# inertial.net
KiCad netlist of a schematic drawn in Altium Designer
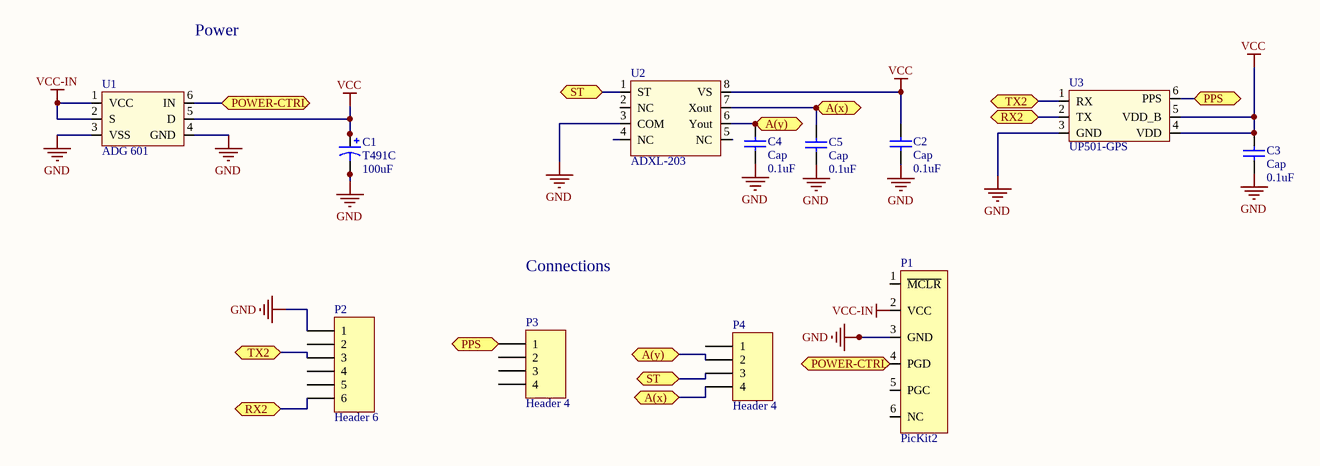
[diagram p0: inertial.SchDoc]

(export (version "E")
  (design (tool "Eeschema 10.0.6"))
  (components
    (comp (ref "C1")
      (value "T491C")
      (footprint "C")
      (description "Solid Tantalum Chip Capacitor, Standard T491 Series - Industrial Grade")
      (fields (field (name "ALTIUM_VALUE") "100uF") (field (name "PUBLISHER") "Altium Limited"))
      (libsource (lib "KEMET Chip Capacitor") (part "T491C"))
    )
    (comp (ref "C2")
      (value "Cap")
      (footprint "C1206")
      (description "Capacitor")
      (fields (field (name "ALTIUM_VALUE") "0.1uF") (field (name "PUBLISHER") "Altium Limited"))
      (libsource (lib "Miscellaneous Devices") (part "Cap"))
    )
    (comp (ref "C3")
      (value "Cap")
      (footprint "C1206")
      (description "Capacitor")
      (fields (field (name "ALTIUM_VALUE") "0.1uF") (field (name "PUBLISHER") "Altium Limited"))
      (libsource (lib "Miscellaneous Devices") (part "Cap"))
    )
    (comp (ref "C4")
      (value "Cap")
      (footprint "C1206")
      (description "Capacitor")
      (fields (field (name "ALTIUM_VALUE") "0.1uF") (field (name "PUBLISHER") "Altium Limited"))
      (libsource (lib "Miscellaneous Devices") (part "Cap"))
    )
    (comp (ref "C5")
      (value "Cap")
      (footprint "C1206")
      (description "Capacitor")
      (fields (field (name "ALTIUM_VALUE") "0.1uF") (field (name "PUBLISHER") "Altium Limited"))
      (libsource (lib "Miscellaneous Devices") (part "Cap"))
    )
    (comp (ref "P1") (value "PicKit2") (footprint "PICKIT3") (libsource (lib "uMote") (part "PicKit2")))
    (comp (ref "P2")
      (value "Header 6")
      (footprint "HDR1X6")
      (description "Header, 6-Pin")
      (fields (field (name "PUBLISHER") "Altium Limited"))
      (libsource (lib "Miscellaneous Connectors") (part "Header 6"))
    )
    (comp (ref "P3")
      (value "Header 4")
      (footprint "HDR1X4")
      (description "Header, 4-Pin")
      (fields (field (name "PUBLISHER") "Altium Limited"))
      (libsource (lib "Miscellaneous Connectors") (part "Header 4"))
    )
    (comp (ref "P4")
      (value "Header 4")
      (footprint "HDR1X4")
      (description "Header, 4-Pin")
      (fields (field (name "PUBLISHER") "Altium Limited"))
      (libsource (lib "Miscellaneous Connectors") (part "Header 4"))
    )
    (comp (ref "U1") (value "ADG 601") (footprint "SOT26A-6N") (libsource (lib "uMote") (part "ADG 601")))
    (comp (ref "U2") (value "ADXL-203") (footprint "ADXL-203") (libsource (lib "uMote") (part "ADXL-203")))
    (comp (ref "U3") (value "UP501-GPS") (footprint "UP501-GPS") (libsource (lib "uMote") (part "UP501-GPS")))
  )
  (nets
    (net (code "1") (name "/A(x)") (class "Default")
      (node (ref "C5") (pin "1") (pinfunction "1_1") (pintype "passive"))
      (node (ref "P4") (pin "4") (pinfunction "4_4") (pintype "passive"))
      (node (ref "U2") (pin "7") (pinfunction "Xout_7") (pintype "passive"))
    )
    (net (code "2") (name "/A(y)") (class "Default")
      (node (ref "C4") (pin "1") (pinfunction "1_1") (pintype "passive"))
      (node (ref "P4") (pin "2") (pinfunction "2_2") (pintype "passive"))
      (node (ref "U2") (pin "6") (pinfunction "Yout_6") (pintype "passive"))
    )
    (net (code "3") (name "/POWER-CTRL") (class "Default")
      (node (ref "P1") (pin "4") (pinfunction "PGD_4") (pintype "passive"))
      (node (ref "U1") (pin "6") (pinfunction "IN_6") (pintype "passive"))
    )
    (net (code "4") (name "/PPS") (class "Default")
      (node (ref "P3") (pin "1") (pinfunction "1_1") (pintype "passive"))
      (node (ref "U3") (pin "6") (pinfunction "PPS_6") (pintype "passive"))
    )
    (net (code "5") (name "/RX2") (class "Default")
      (node (ref "P2") (pin "6") (pinfunction "6_6") (pintype "passive"))
      (node (ref "U3") (pin "2") (pinfunction "TX_2") (pintype "passive"))
    )
    (net (code "6") (name "/ST") (class "Default")
      (node (ref "P4") (pin "3") (pinfunction "3_3") (pintype "passive"))
      (node (ref "U2") (pin "1") (pinfunction "ST_1") (pintype "passive"))
    )
    (net (code "7") (name "/TX2") (class "Default")
      (node (ref "P2") (pin "3") (pinfunction "3_3") (pintype "passive"))
      (node (ref "U3") (pin "1") (pinfunction "RX_1") (pintype "passive"))
    )
    (net (code "8") (name "GND") (class "Default")
      (node (ref "C1") (pin "2") (pinfunction "2_2") (pintype "passive"))
      (node (ref "C2") (pin "2") (pinfunction "2_2") (pintype "passive"))
      (node (ref "C3") (pin "2") (pinfunction "2_2") (pintype "passive"))
      (node (ref "C4") (pin "2") (pinfunction "2_2") (pintype "passive"))
      (node (ref "C5") (pin "2") (pinfunction "2_2") (pintype "passive"))
      (node (ref "P1") (pin "3") (pinfunction "GND_3") (pintype "passive"))
      (node (ref "P2") (pin "1") (pinfunction "1_1") (pintype "passive"))
      (node (ref "U1") (pin "3") (pinfunction "VSS_3") (pintype "passive"))
      (node (ref "U1") (pin "4") (pinfunction "GND_4") (pintype "passive"))
      (node (ref "U2") (pin "3") (pinfunction "COM_3") (pintype "passive"))
      (node (ref "U3") (pin "3") (pinfunction "GND_3") (pintype "passive"))
    )
    (net (code "9") (name "VCC") (class "Default")
      (node (ref "C1") (pin "1") (pinfunction "1_1") (pintype "passive"))
      (node (ref "C2") (pin "1") (pinfunction "1_1") (pintype "passive"))
      (node (ref "C3") (pin "1") (pinfunction "1_1") (pintype "passive"))
      (node (ref "U1") (pin "5") (pinfunction "D_5") (pintype "passive"))
      (node (ref "U2") (pin "8") (pinfunction "VS_8") (pintype "passive"))
      (node (ref "U3") (pin "4") (pinfunction "VDD_4") (pintype "passive"))
      (node (ref "U3") (pin "5") (pinfunction "VDD_B_5") (pintype "passive"))
    )
    (net (code "10") (name "VCC-IN") (class "Default")
      (node (ref "P1") (pin "2") (pinfunction "VCC_2") (pintype "passive"))
      (node (ref "U1") (pin "1") (pinfunction "VCC_1") (pintype "passive"))
      (node (ref "U1") (pin "2") (pinfunction "S_2") (pintype "passive"))
    )
    (net (code "11") (name "unconnected-(P1-MCLR-Pad1)") (class "Default")
      (node (ref "P1") (pin "1") (pinfunction "MCLR_1") (pintype "passive"))
    )
    (net (code "12") (name "unconnected-(P1-NC-Pad6)") (class "Default")
      (node (ref "P1") (pin "6") (pinfunction "NC_6") (pintype "passive"))
    )
    (net (code "13") (name "unconnected-(P1-PGC-Pad5)") (class "Default")
      (node (ref "P1") (pin "5") (pinfunction "PGC_5") (pintype "passive"))
    )
    (net (code "14") (name "unconnected-(P2-Pad2)") (class "Default")
      (node (ref "P2") (pin "2") (pinfunction "2_2") (pintype "passive"))
    )
    (net (code "15") (name "unconnected-(P2-Pad4)") (class "Default")
      (node (ref "P2") (pin "4") (pinfunction "4_4") (pintype "passive"))
    )
    (net (code "16") (name "unconnected-(P2-Pad5)") (class "Default")
      (node (ref "P2") (pin "5") (pinfunction "5_5") (pintype "passive"))
    )
    (net (code "17") (name "unconnected-(P3-Pad2)") (class "Default")
      (node (ref "P3") (pin "2") (pinfunction "2_2") (pintype "passive"))
    )
    (net (code "18") (name "unconnected-(P3-Pad3)") (class "Default")
      (node (ref "P3") (pin "3") (pinfunction "3_3") (pintype "passive"))
    )
    (net (code "19") (name "unconnected-(P3-Pad4)") (class "Default")
      (node (ref "P3") (pin "4") (pinfunction "4_4") (pintype "passive"))
    )
    (net (code "20") (name "unconnected-(P4-Pad1)") (class "Default")
      (node (ref "P4") (pin "1") (pinfunction "1_1") (pintype "passive"))
    )
    (net (code "21") (name "unconnected-(U2-NC-Pad2)") (class "Default")
      (node (ref "U2") (pin "2") (pinfunction "NC_2") (pintype "passive"))
    )
    (net (code "22") (name "unconnected-(U2-NC-Pad4)") (class "Default")
      (node (ref "U2") (pin "4") (pinfunction "NC_4") (pintype "passive"))
    )
    (net (code "23") (name "unconnected-(U2-NC-Pad5)") (class "Default")
      (node (ref "U2") (pin "5") (pinfunction "NC_5") (pintype "passive"))
    )
  )
)
